# FPGA_Power.net
KiCad netlist of a schematic drawn in Altium Designer
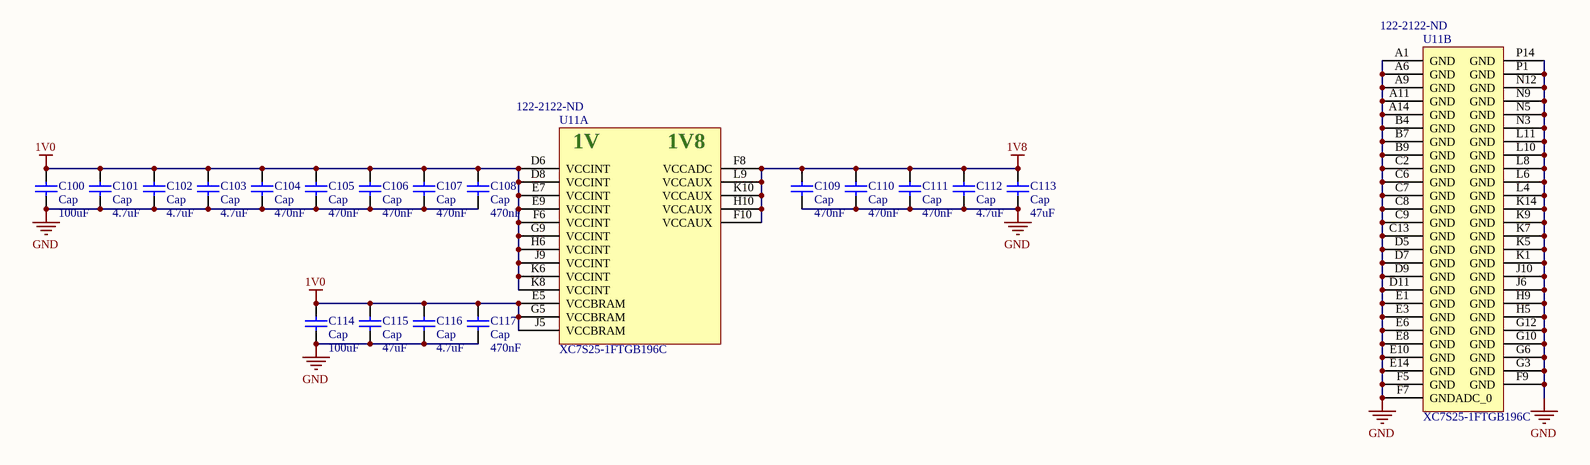
[diagram p0: FPGA Power.SchDoc]

(export (version "E")
  (design (tool "Eeschema 10.0.6"))
  (components
    (comp (ref "C100")
      (value "Cap")
      (footprint "C1210")
      (description "Capacitor")
      (fields (field (name "ALTIUM_VALUE") "100uF") (field (name "PUBLISHER") "Altium Limited"))
      (libsource (lib "Miscellaneous Devices") (part "Cap"))
    )
    (comp (ref "C101")
      (value "Cap")
      (footprint "6-0805_M")
      (description "Capacitor")
      (fields (field (name "ALTIUM_VALUE") "4.7uF") (field (name "PUBLISHER") "Altium Limited"))
      (libsource (lib "Miscellaneous Devices") (part "Cap"))
    )
    (comp (ref "C102")
      (value "Cap")
      (footprint "6-0805_M")
      (description "Capacitor")
      (fields (field (name "ALTIUM_VALUE") "4.7uF") (field (name "PUBLISHER") "Altium Limited"))
      (libsource (lib "Miscellaneous Devices") (part "Cap"))
    )
    (comp (ref "C103")
      (value "Cap")
      (footprint "6-0805_M")
      (description "Capacitor")
      (fields (field (name "ALTIUM_VALUE") "4.7uF") (field (name "PUBLISHER") "Altium Limited"))
      (libsource (lib "Miscellaneous Devices") (part "Cap"))
    )
    (comp (ref "C104")
      (value "Cap")
      (footprint "1608[0603]")
      (description "Capacitor")
      (fields (field (name "ALTIUM_VALUE") "470nF") (field (name "PUBLISHER") "Altium Limited"))
      (libsource (lib "Miscellaneous Devices") (part "Cap"))
    )
    (comp (ref "C105")
      (value "Cap")
      (footprint "1608[0603]")
      (description "Capacitor")
      (fields (field (name "ALTIUM_VALUE") "470nF") (field (name "PUBLISHER") "Altium Limited"))
      (libsource (lib "Miscellaneous Devices") (part "Cap"))
    )
    (comp (ref "C106")
      (value "Cap")
      (footprint "1608[0603]")
      (description "Capacitor")
      (fields (field (name "ALTIUM_VALUE") "470nF") (field (name "PUBLISHER") "Altium Limited"))
      (libsource (lib "Miscellaneous Devices") (part "Cap"))
    )
    (comp (ref "C107")
      (value "Cap")
      (footprint "1608[0603]")
      (description "Capacitor")
      (fields (field (name "ALTIUM_VALUE") "470nF") (field (name "PUBLISHER") "Altium Limited"))
      (libsource (lib "Miscellaneous Devices") (part "Cap"))
    )
    (comp (ref "C108")
      (value "Cap")
      (footprint "1608[0603]")
      (description "Capacitor")
      (fields (field (name "ALTIUM_VALUE") "470nF") (field (name "PUBLISHER") "Altium Limited"))
      (libsource (lib "Miscellaneous Devices") (part "Cap"))
    )
    (comp (ref "C109")
      (value "Cap")
      (footprint "1608[0603]")
      (description "Capacitor")
      (fields (field (name "ALTIUM_VALUE") "470nF") (field (name "PUBLISHER") "Altium Limited"))
      (libsource (lib "Miscellaneous Devices") (part "Cap"))
    )
    (comp (ref "C110")
      (value "Cap")
      (footprint "1608[0603]")
      (description "Capacitor")
      (fields (field (name "ALTIUM_VALUE") "470nF") (field (name "PUBLISHER") "Altium Limited"))
      (libsource (lib "Miscellaneous Devices") (part "Cap"))
    )
    (comp (ref "C111")
      (value "Cap")
      (footprint "1608[0603]")
      (description "Capacitor")
      (fields (field (name "ALTIUM_VALUE") "470nF") (field (name "PUBLISHER") "Altium Limited"))
      (libsource (lib "Miscellaneous Devices") (part "Cap"))
    )
    (comp (ref "C112")
      (value "Cap")
      (footprint "6-0805_M")
      (description "Capacitor")
      (fields (field (name "ALTIUM_VALUE") "4.7uF") (field (name "PUBLISHER") "Altium Limited"))
      (libsource (lib "Miscellaneous Devices") (part "Cap"))
    )
    (comp (ref "C113")
      (value "Cap")
      (footprint "C1210")
      (description "Capacitor")
      (fields (field (name "ALTIUM_VALUE") "47uF") (field (name "PUBLISHER") "Altium Limited"))
      (libsource (lib "Miscellaneous Devices") (part "Cap"))
    )
    (comp (ref "C114")
      (value "Cap")
      (footprint "C1210")
      (description "Capacitor")
      (fields (field (name "ALTIUM_VALUE") "100uF") (field (name "PUBLISHER") "Altium Limited"))
      (libsource (lib "Miscellaneous Devices") (part "Cap"))
    )
    (comp (ref "C115")
      (value "Cap")
      (footprint "C1210")
      (description "Capacitor")
      (fields (field (name "ALTIUM_VALUE") "47uF") (field (name "PUBLISHER") "Altium Limited"))
      (libsource (lib "Miscellaneous Devices") (part "Cap"))
    )
    (comp (ref "C116")
      (value "Cap")
      (footprint "6-0805_M")
      (description "Capacitor")
      (fields (field (name "ALTIUM_VALUE") "4.7uF") (field (name "PUBLISHER") "Altium Limited"))
      (libsource (lib "Miscellaneous Devices") (part "Cap"))
    )
    (comp (ref "C117")
      (value "Cap")
      (footprint "1608[0603]")
      (description "Capacitor")
      (fields (field (name "ALTIUM_VALUE") "470nF") (field (name "PUBLISHER") "Altium Limited"))
      (libsource (lib "Miscellaneous Devices") (part "Cap"))
    )
    (comp (ref "U11")
      (value "XC7S25-1FTGB196C")
      (footprint "FTGB196 Package")
      (fields (field (name "SUPPLIER PART NUMBER 1") "122-2122-ND"))
      (libsource (lib "XC7S25-1FTGB196C") (part "XC7S25-1FTGB196C"))
    )
  )
  (nets
    (net (code "1") (name "1V0") (class "Default")
      (node (ref "C100") (pin "2") (pinfunction "2_2") (pintype "passive"))
      (node (ref "C101") (pin "2") (pinfunction "2_2") (pintype "passive"))
      (node (ref "C102") (pin "2") (pinfunction "2_2") (pintype "passive"))
      (node (ref "C103") (pin "2") (pinfunction "2_2") (pintype "passive"))
      (node (ref "C104") (pin "2") (pinfunction "2_2") (pintype "passive"))
      (node (ref "C105") (pin "2") (pinfunction "2_2") (pintype "passive"))
      (node (ref "C106") (pin "2") (pinfunction "2_2") (pintype "passive"))
      (node (ref "C107") (pin "2") (pinfunction "2_2") (pintype "passive"))
      (node (ref "C108") (pin "2") (pinfunction "2_2") (pintype "passive"))
      (node (ref "C114") (pin "2") (pinfunction "2_2") (pintype "passive"))
      (node (ref "C115") (pin "2") (pinfunction "2_2") (pintype "passive"))
      (node (ref "C116") (pin "2") (pinfunction "2_2") (pintype "passive"))
      (node (ref "C117") (pin "2") (pinfunction "2_2") (pintype "passive"))
      (node (ref "U11") (pin "D6") (pinfunction "VCCINT_D6") (pintype "power_in"))
      (node (ref "U11") (pin "D8") (pinfunction "VCCINT_D8") (pintype "power_in"))
      (node (ref "U11") (pin "E5") (pinfunction "VCCBRAM_E5") (pintype "power_in"))
      (node (ref "U11") (pin "E7") (pinfunction "VCCINT_E7") (pintype "power_in"))
      (node (ref "U11") (pin "E9") (pinfunction "VCCINT_E9") (pintype "power_in"))
      (node (ref "U11") (pin "F6") (pinfunction "VCCINT_F6") (pintype "power_in"))
      (node (ref "U11") (pin "G5") (pinfunction "VCCBRAM_G5") (pintype "power_in"))
      (node (ref "U11") (pin "G9") (pinfunction "VCCINT_G9") (pintype "power_in"))
      (node (ref "U11") (pin "H6") (pinfunction "VCCINT_H6") (pintype "power_in"))
      (node (ref "U11") (pin "J5") (pinfunction "VCCBRAM_J5") (pintype "power_in"))
      (node (ref "U11") (pin "J9") (pinfunction "VCCINT_J9") (pintype "power_in"))
      (node (ref "U11") (pin "K6") (pinfunction "VCCINT_K6") (pintype "power_in"))
      (node (ref "U11") (pin "K8") (pinfunction "VCCINT_K8") (pintype "power_in"))
    )
    (net (code "2") (name "1V8") (class "Default")
      (node (ref "C109") (pin "2") (pinfunction "2_2") (pintype "passive"))
      (node (ref "C110") (pin "2") (pinfunction "2_2") (pintype "passive"))
      (node (ref "C111") (pin "2") (pinfunction "2_2") (pintype "passive"))
      (node (ref "C112") (pin "2") (pinfunction "2_2") (pintype "passive"))
      (node (ref "C113") (pin "2") (pinfunction "2_2") (pintype "passive"))
      (node (ref "U11") (pin "F10") (pinfunction "VCCAUX_F10") (pintype "power_in"))
      (node (ref "U11") (pin "F8") (pinfunction "VCCADC_F8") (pintype "passive"))
      (node (ref "U11") (pin "H10") (pinfunction "VCCAUX_H10") (pintype "power_in"))
      (node (ref "U11") (pin "K10") (pinfunction "VCCAUX_K10") (pintype "power_in"))
      (node (ref "U11") (pin "L9") (pinfunction "VCCAUX_L9") (pintype "power_in"))
    )
    (net (code "3") (name "GND") (class "Default")
      (node (ref "C100") (pin "1") (pinfunction "1_1") (pintype "passive"))
      (node (ref "C101") (pin "1") (pinfunction "1_1") (pintype "passive"))
      (node (ref "C102") (pin "1") (pinfunction "1_1") (pintype "passive"))
      (node (ref "C103") (pin "1") (pinfunction "1_1") (pintype "passive"))
      (node (ref "C104") (pin "1") (pinfunction "1_1") (pintype "passive"))
      (node (ref "C105") (pin "1") (pinfunction "1_1") (pintype "passive"))
      (node (ref "C106") (pin "1") (pinfunction "1_1") (pintype "passive"))
      (node (ref "C107") (pin "1") (pinfunction "1_1") (pintype "passive"))
      (node (ref "C108") (pin "1") (pinfunction "1_1") (pintype "passive"))
      (node (ref "C109") (pin "1") (pinfunction "1_1") (pintype "passive"))
      (node (ref "C110") (pin "1") (pinfunction "1_1") (pintype "passive"))
      (node (ref "C111") (pin "1") (pinfunction "1_1") (pintype "passive"))
      (node (ref "C112") (pin "1") (pinfunction "1_1") (pintype "passive"))
      (node (ref "C113") (pin "1") (pinfunction "1_1") (pintype "passive"))
      (node (ref "C114") (pin "1") (pinfunction "1_1") (pintype "passive"))
      (node (ref "C115") (pin "1") (pinfunction "1_1") (pintype "passive"))
      (node (ref "C116") (pin "1") (pinfunction "1_1") (pintype "passive"))
      (node (ref "C117") (pin "1") (pinfunction "1_1") (pintype "passive"))
      (node (ref "U11") (pin "A1") (pinfunction "GND_A1") (pintype "power_in"))
      (node (ref "U11") (pin "A11") (pinfunction "GND_A11") (pintype "power_in"))
      (node (ref "U11") (pin "A14") (pinfunction "GND_A14") (pintype "power_in"))
      (node (ref "U11") (pin "A6") (pinfunction "GND_A6") (pintype "power_in"))
      (node (ref "U11") (pin "A9") (pinfunction "GND_A9") (pintype "power_in"))
      (node (ref "U11") (pin "B4") (pinfunction "GND_B4") (pintype "power_in"))
      (node (ref "U11") (pin "B7") (pinfunction "GND_B7") (pintype "power_in"))
      (node (ref "U11") (pin "B9") (pinfunction "GND_B9") (pintype "power_in"))
      (node (ref "U11") (pin "C13") (pinfunction "GND_C13") (pintype "power_in"))
      (node (ref "U11") (pin "C2") (pinfunction "GND_C2") (pintype "power_in"))
      (node (ref "U11") (pin "C6") (pinfunction "GND_C6") (pintype "power_in"))
      (node (ref "U11") (pin "C7") (pinfunction "GND_C7") (pintype "power_in"))
      (node (ref "U11") (pin "C8") (pinfunction "GND_C8") (pintype "power_in"))
      (node (ref "U11") (pin "C9") (pinfunction "GND_C9") (pintype "power_in"))
      (node (ref "U11") (pin "D11") (pinfunction "GND_D11") (pintype "power_in"))
      (node (ref "U11") (pin "D5") (pinfunction "GND_D5") (pintype "power_in"))
      (node (ref "U11") (pin "D7") (pinfunction "GND_D7") (pintype "power_in"))
      (node (ref "U11") (pin "D9") (pinfunction "GND_D9") (pintype "power_in"))
      (node (ref "U11") (pin "E1") (pinfunction "GND_E1") (pintype "power_in"))
      (node (ref "U11") (pin "E10") (pinfunction "GND_E10") (pintype "power_in"))
      (node (ref "U11") (pin "E14") (pinfunction "GND_E14") (pintype "power_in"))
      (node (ref "U11") (pin "E3") (pinfunction "GND_E3") (pintype "power_in"))
      (node (ref "U11") (pin "E6") (pinfunction "GND_E6") (pintype "power_in"))
      (node (ref "U11") (pin "E8") (pinfunction "GND_E8") (pintype "power_in"))
      (node (ref "U11") (pin "F5") (pinfunction "GND_F5") (pintype "power_in"))
      (node (ref "U11") (pin "F7") (pinfunction "GNDADC_0_F7") (pintype "passive"))
      (node (ref "U11") (pin "F9") (pinfunction "GND_F9") (pintype "power_in"))
      (node (ref "U11") (pin "G10") (pinfunction "GND_G10") (pintype "power_in"))
      (node (ref "U11") (pin "G12") (pinfunction "GND_G12") (pintype "power_in"))
      (node (ref "U11") (pin "G3") (pinfunction "GND_G3") (pintype "power_in"))
      (node (ref "U11") (pin "G6") (pinfunction "GND_G6") (pintype "power_in"))
      (node (ref "U11") (pin "H5") (pinfunction "GND_H5") (pintype "power_in"))
      (node (ref "U11") (pin "H9") (pinfunction "GND_H9") (pintype "power_in"))
      (node (ref "U11") (pin "J10") (pinfunction "GND_J10") (pintype "power_in"))
      (node (ref "U11") (pin "J6") (pinfunction "GND_J6") (pintype "power_in"))
      (node (ref "U11") (pin "K1") (pinfunction "GND_K1") (pintype "power_in"))
      (node (ref "U11") (pin "K14") (pinfunction "GND_K14") (pintype "power_in"))
      (node (ref "U11") (pin "K5") (pinfunction "GND_K5") (pintype "power_in"))
      (node (ref "U11") (pin "K7") (pinfunction "GND_K7") (pintype "power_in"))
      (node (ref "U11") (pin "K9") (pinfunction "GND_K9") (pintype "power_in"))
      (node (ref "U11") (pin "L10") (pinfunction "GND_L10") (pintype "power_in"))
      (node (ref "U11") (pin "L11") (pinfunction "GND_L11") (pintype "power_in"))
      (node (ref "U11") (pin "L4") (pinfunction "GND_L4") (pintype "power_in"))
      (node (ref "U11") (pin "L6") (pinfunction "GND_L6") (pintype "power_in"))
      (node (ref "U11") (pin "L8") (pinfunction "GND_L8") (pintype "power_in"))
      (node (ref "U11") (pin "N12") (pinfunction "GND_N12") (pintype "power_in"))
      (node (ref "U11") (pin "N3") (pinfunction "GND_N3") (pintype "power_in"))
      (node (ref "U11") (pin "N5") (pinfunction "GND_N5") (pintype "power_in"))
      (node (ref "U11") (pin "N9") (pinfunction "GND_N9") (pintype "power_in"))
      (node (ref "U11") (pin "P1") (pinfunction "GND_P1") (pintype "power_in"))
      (node (ref "U11") (pin "P14") (pinfunction "GND_P14") (pintype "power_in"))
    )
  )
)
